# ui_bt_audio.net
KiCad netlist of a schematic drawn in Altium Designer
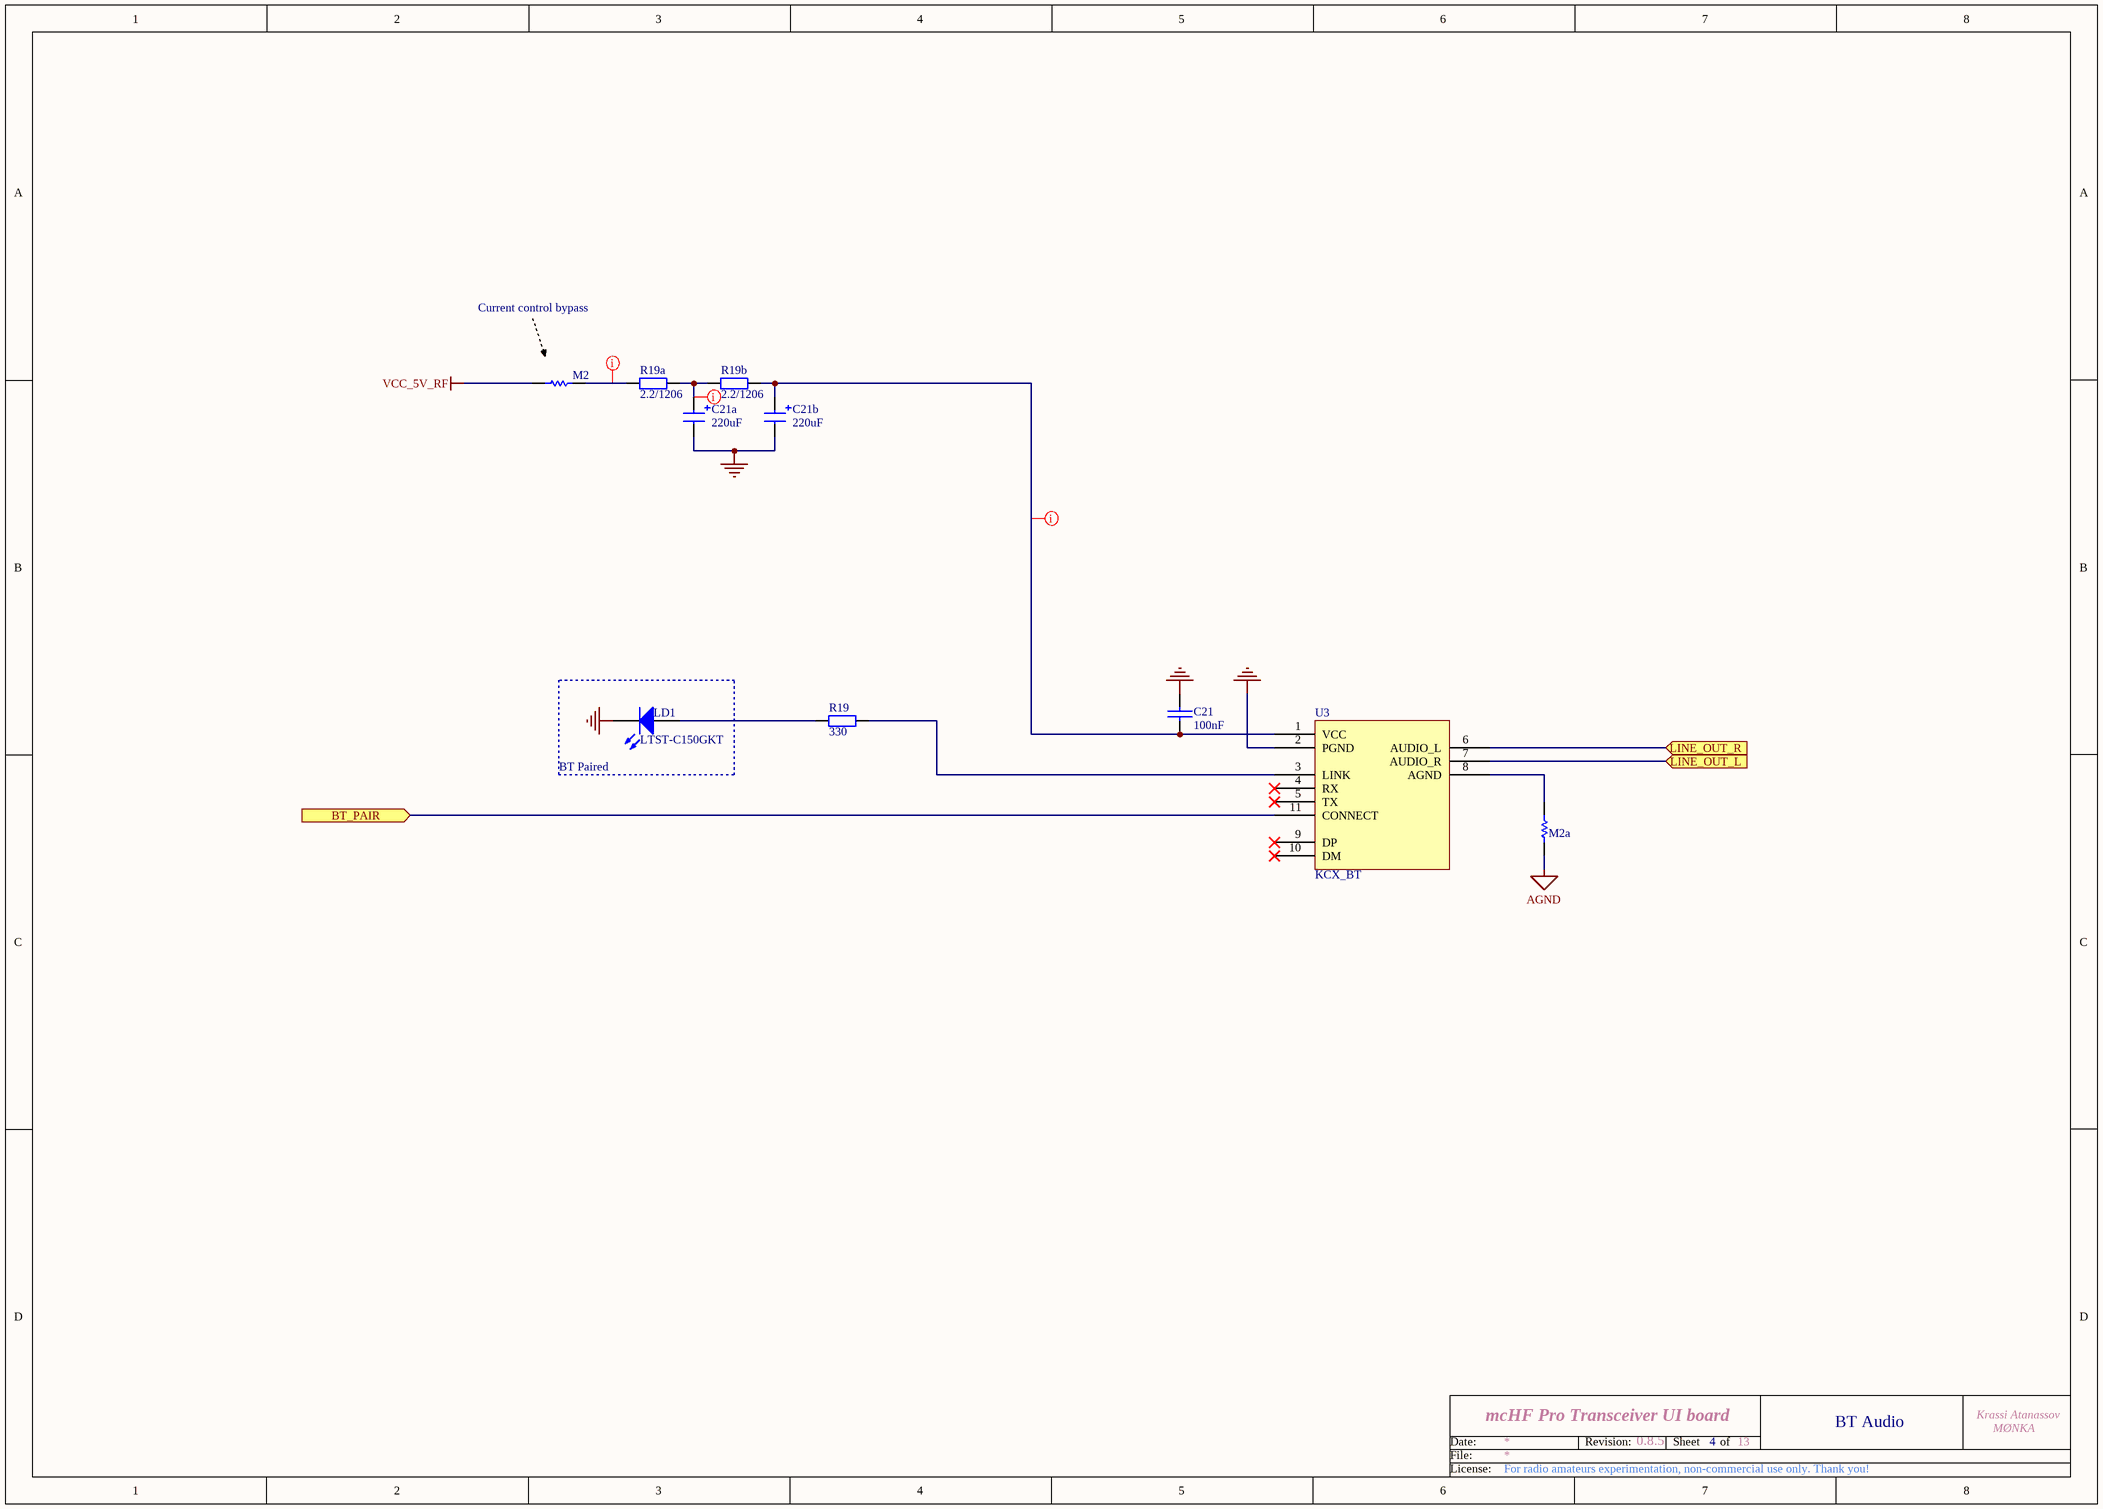
[diagram p0: ui_bt_audio.SchDoc]

(export (version "E")
  (design (tool "Eeschema 10.0.6"))
  (components
    (comp (ref "C21")
      (value "100nF")
      (footprint "0805")
      (description "Capacitor")
      (libsource (lib "*") (part "CAP"))
    )
    (comp (ref "C21a")
      (value "220uF")
      (footprint "CAP_ALUM_Pro")
      (description "Electrolitic capacitor")
      (libsource (lib "mcHF_ui") (part "CAP-POL"))
    )
    (comp (ref "C21b")
      (value "220uF")
      (footprint "CAP_ALUM_Pro")
      (description "Electrolitic capacitor")
      (libsource (lib "mcHF_ui") (part "CAP-POL"))
    )
    (comp (ref "LD1")
      (value "LTST-C150GKT")
      (footprint "1206_Elec_Cap")
      (description "LED 3mm")
      (libsource (lib "mcHF_ui") (part "LED2"))
    )
    (comp (ref "M2")
      (value "0")
      (footprint "SB_0603")
      (description "Link")
      (fields (field (name "PUBLISHER") "Altium Limited"))
      (libsource (lib "__ui") (part "Link"))
    )
    (comp (ref "M2a")
      (value "0")
      (footprint "SB_0603")
      (description "Link")
      (fields (field (name "PUBLISHER") "Altium Limited"))
      (libsource (lib "__ui") (part "Link"))
    )
    (comp (ref "R19")
      (value "330")
      (footprint "0805")
      (description "Resistor")
      (libsource (lib "") (part "RES_1"))
    )
    (comp (ref "R19a")
      (value "2.2/1206")
      (footprint "1206")
      (description "Resistor")
      (libsource (lib "mcHF_ui") (part "RES"))
    )
    (comp (ref "R19b")
      (value "2.2/1206")
      (footprint "1206")
      (description "Resistor")
      (libsource (lib "mcHF_ui") (part "RES"))
    )
    (comp (ref "U3")
      (value "KCX_BT")
      (footprint "KCX_BT")
      (description "KCX_BT_EMITTER V 1.7")
      (libsource (lib "__ui") (part "KCX_BT"))
    )
  )
  (nets
    (net (code "1") (name "/BT_PAIR") (class "Default")
      (node (ref "U3") (pin "11") (pinfunction "CONNECT_11") (pintype "passive"))
    )
    (net (code "2") (name "/LINE_OUT_L") (class "Default")
      (node (ref "U3") (pin "7") (pinfunction "AUDIO_R_7") (pintype "passive"))
    )
    (net (code "3") (name "/LINE_OUT_R") (class "Default")
      (node (ref "U3") (pin "6") (pinfunction "AUDIO_L_6") (pintype "passive"))
    )
    (net (code "4") (name "AGND") (class "Default")
      (node (ref "M2a") (pin "1") (pinfunction "1_1") (pintype "passive"))
    )
    (net (code "5") (name "GND") (class "Default")
      (node (ref "C21") (pin "1") (pinfunction "1_1") (pintype "passive"))
      (node (ref "C21a") (pin "2") (pinfunction "2_2") (pintype "passive"))
      (node (ref "C21b") (pin "2") (pinfunction "2_2") (pintype "passive"))
      (node (ref "LD1") (pin "2") (pinfunction "K_2") (pintype "passive"))
      (node (ref "U3") (pin "2") (pinfunction "PGND_2") (pintype "passive"))
    )
    (net (code "6") (name "Net-(C21a-Pad1)") (class "Default")
      (node (ref "C21a") (pin "1") (pinfunction "1_1") (pintype "passive"))
      (node (ref "R19a") (pin "2") (pinfunction "2_2") (pintype "passive"))
      (node (ref "R19b") (pin "1") (pinfunction "1_1") (pintype "passive"))
    )
    (net (code "7") (name "Net-(LD1-A)") (class "Default")
      (node (ref "LD1") (pin "1") (pinfunction "A_1") (pintype "passive"))
      (node (ref "R19") (pin "2") (pinfunction "2_2") (pintype "passive"))
    )
    (net (code "8") (name "Net-(M2-Pad2)") (class "Default")
      (node (ref "M2") (pin "2") (pinfunction "2_2") (pintype "passive"))
      (node (ref "R19a") (pin "1") (pinfunction "1_1") (pintype "passive"))
    )
    (net (code "9") (name "Net-(U3-AGND)") (class "Default")
      (node (ref "M2a") (pin "2") (pinfunction "2_2") (pintype "passive"))
      (node (ref "U3") (pin "8") (pinfunction "AGND_8") (pintype "passive"))
    )
    (net (code "10") (name "Net-(U3-LINK)") (class "Default")
      (node (ref "R19") (pin "1") (pinfunction "1_1") (pintype "passive"))
      (node (ref "U3") (pin "3") (pinfunction "LINK_3") (pintype "passive"))
    )
    (net (code "11") (name "Net-(U3-VCC)") (class "Default")
      (node (ref "C21") (pin "2") (pinfunction "2_2") (pintype "passive"))
      (node (ref "C21b") (pin "1") (pinfunction "1_1") (pintype "passive"))
      (node (ref "R19b") (pin "2") (pinfunction "2_2") (pintype "passive"))
      (node (ref "U3") (pin "1") (pinfunction "VCC_1") (pintype "passive"))
    )
    (net (code "12") (name "VCC_5V_RF") (class "Default")
      (node (ref "M2") (pin "1") (pinfunction "1_1") (pintype "passive"))
    )
    (net (code "13") (name "unconnected-(U3-DM-Pad10)") (class "Default")
      (node (ref "U3") (pin "10") (pinfunction "DM_10") (pintype "passive+no_connect"))
    )
    (net (code "14") (name "unconnected-(U3-DP-Pad9)") (class "Default")
      (node (ref "U3") (pin "9") (pinfunction "DP_9") (pintype "passive+no_connect"))
    )
    (net (code "15") (name "unconnected-(U3-RX-Pad4)") (class "Default")
      (node (ref "U3") (pin "4") (pinfunction "RX_4") (pintype "passive+no_connect"))
    )
    (net (code "16") (name "unconnected-(U3-TX-Pad5)") (class "Default")
      (node (ref "U3") (pin "5") (pinfunction "TX_5") (pintype "passive+no_connect"))
    )
  )
)
